# peacock3.net
KiCad netlist of a schematic drawn in EAGLE
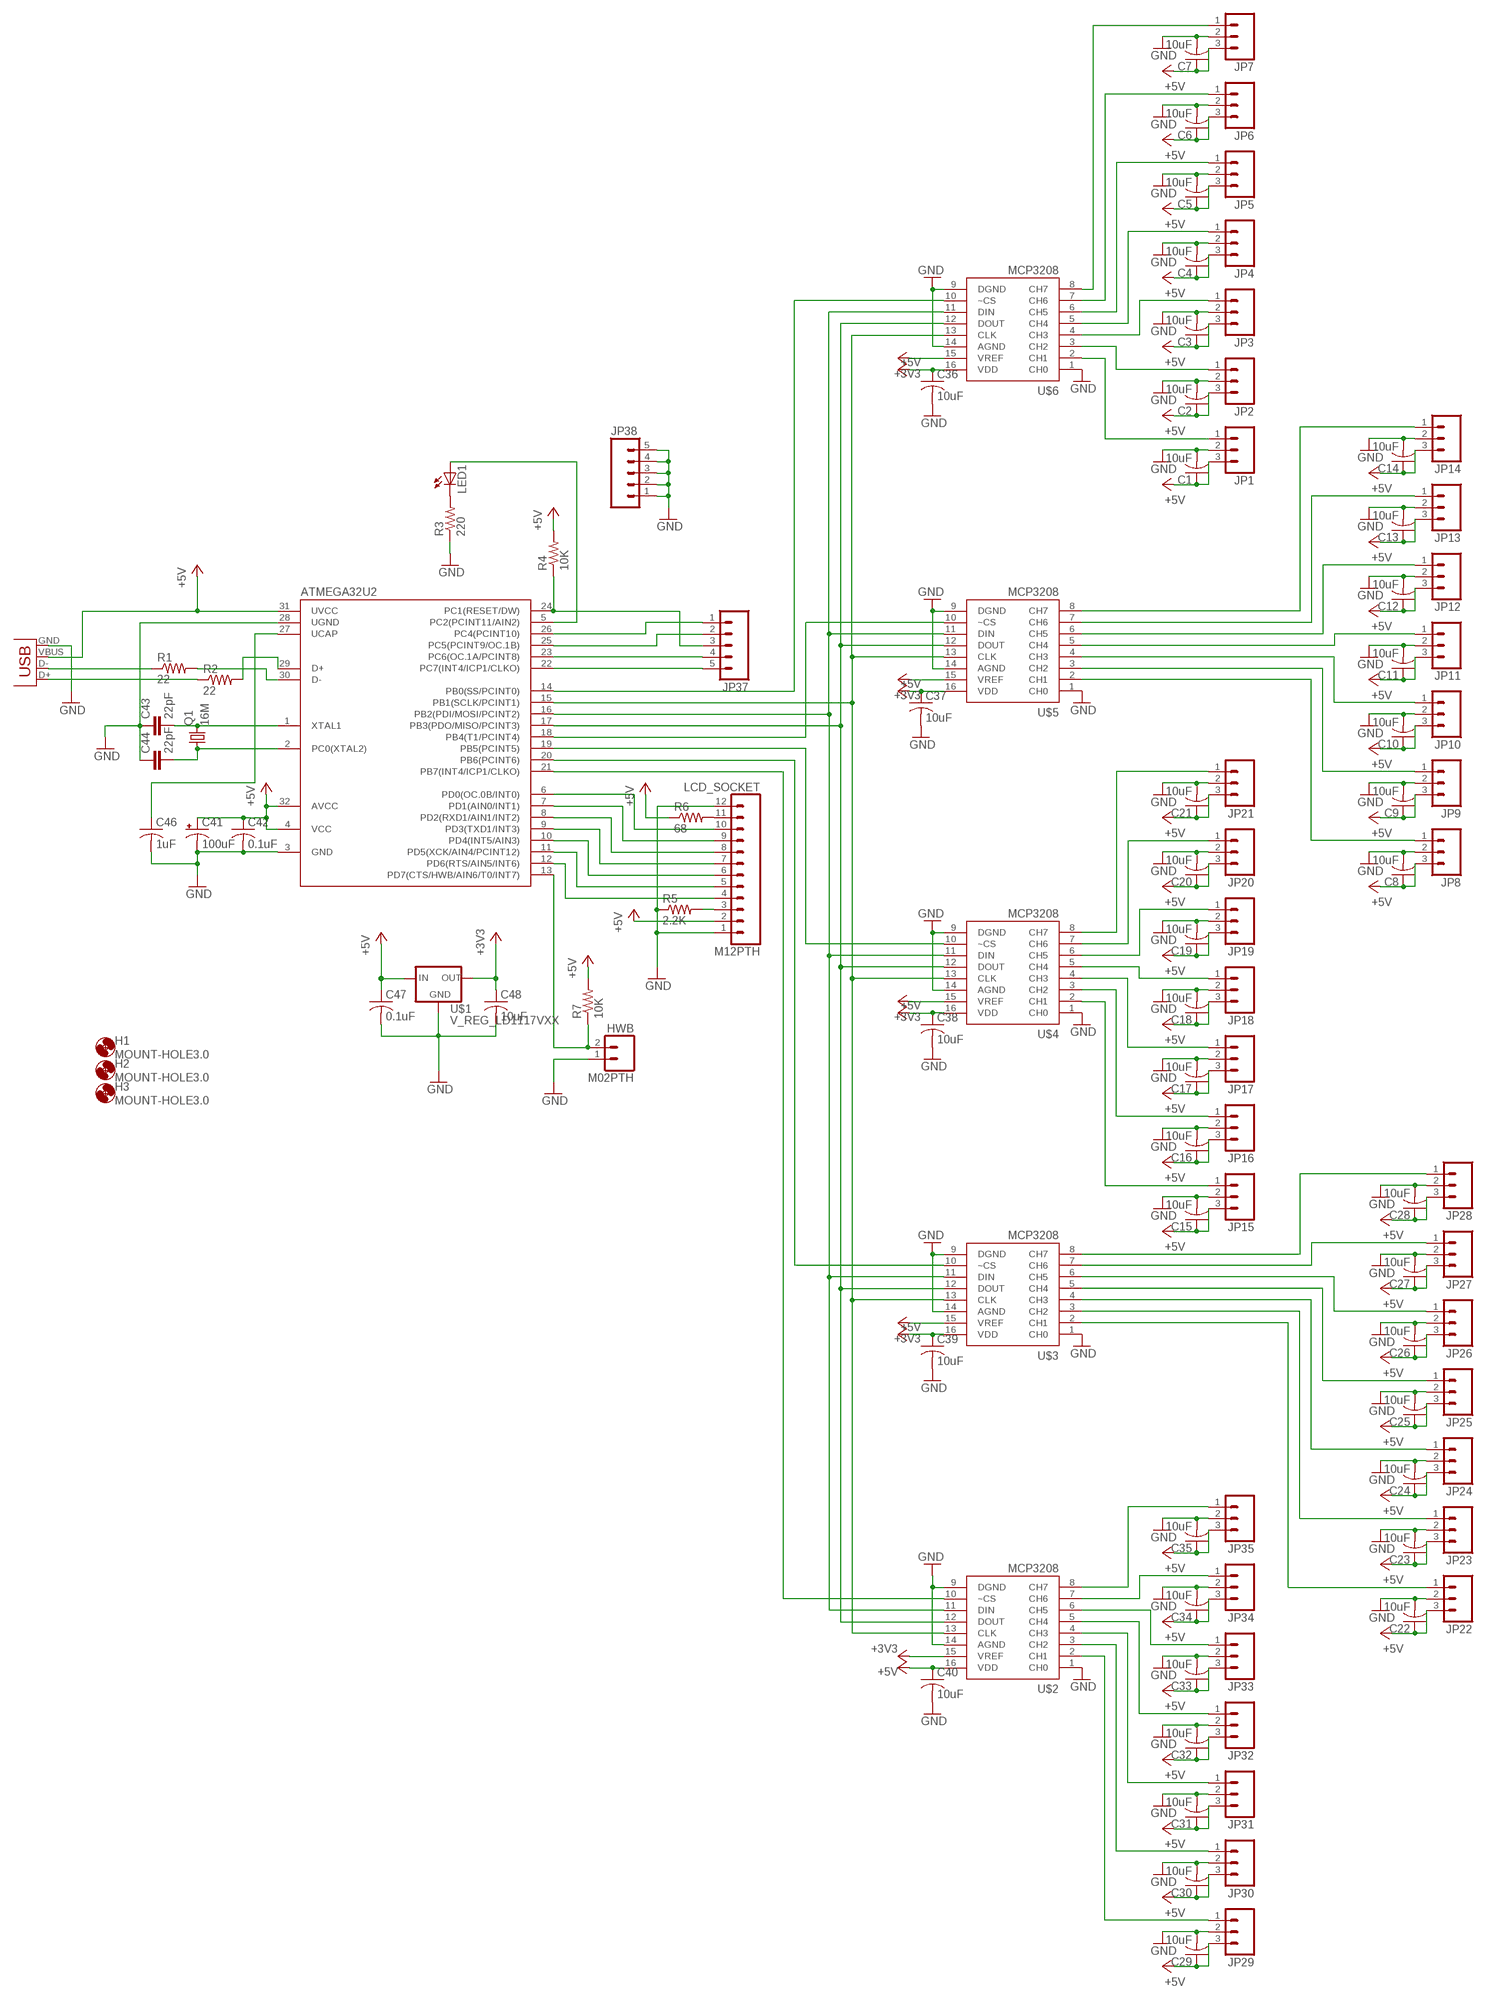
[diagram p0: schematic, sheet 1]

(export (version "E")
  (design (tool "Eeschema 10.0.6"))
  (components
    (comp (ref "ATMEGA32U2")
      (value "ATMEGA32U2")
      (footprint "eagle-import:TQFP32-08")
      (libsource (lib "eagle-import") (part "ATMEGA32U2"))
    )
    (comp (ref "C1")
      (value "10uF")
      (footprint "eagle-import:C1210")
      (libsource (lib "eagle-import") (part "C-USC1210"))
    )
    (comp (ref "C2")
      (value "10uF")
      (footprint "eagle-import:C1210")
      (libsource (lib "eagle-import") (part "C-USC1210"))
    )
    (comp (ref "C3")
      (value "10uF")
      (footprint "eagle-import:C1210")
      (libsource (lib "eagle-import") (part "C-USC1210"))
    )
    (comp (ref "C4")
      (value "10uF")
      (footprint "eagle-import:C1210")
      (libsource (lib "eagle-import") (part "C-USC1210"))
    )
    (comp (ref "C5")
      (value "10uF")
      (footprint "eagle-import:C1210")
      (libsource (lib "eagle-import") (part "C-USC1210"))
    )
    (comp (ref "C6")
      (value "10uF")
      (footprint "eagle-import:C1210")
      (libsource (lib "eagle-import") (part "C-USC1210"))
    )
    (comp (ref "C7")
      (value "10uF")
      (footprint "eagle-import:C1210")
      (libsource (lib "eagle-import") (part "C-USC1210"))
    )
    (comp (ref "C8")
      (value "10uF")
      (footprint "eagle-import:C1210")
      (libsource (lib "eagle-import") (part "C-USC1210"))
    )
    (comp (ref "C9")
      (value "10uF")
      (footprint "eagle-import:C1210")
      (libsource (lib "eagle-import") (part "C-USC1210"))
    )
    (comp (ref "C10")
      (value "10uF")
      (footprint "eagle-import:C1210")
      (libsource (lib "eagle-import") (part "C-USC1210"))
    )
    (comp (ref "C11")
      (value "10uF")
      (footprint "eagle-import:C1210")
      (libsource (lib "eagle-import") (part "C-USC1210"))
    )
    (comp (ref "C12")
      (value "10uF")
      (footprint "eagle-import:C1210")
      (libsource (lib "eagle-import") (part "C-USC1210"))
    )
    (comp (ref "C13")
      (value "10uF")
      (footprint "eagle-import:C1210")
      (libsource (lib "eagle-import") (part "C-USC1210"))
    )
    (comp (ref "C14")
      (value "10uF")
      (footprint "eagle-import:C1210")
      (libsource (lib "eagle-import") (part "C-USC1210"))
    )
    (comp (ref "C15")
      (value "10uF")
      (footprint "eagle-import:C1210")
      (libsource (lib "eagle-import") (part "C-USC1210"))
    )
    (comp (ref "C16")
      (value "10uF")
      (footprint "eagle-import:C1210")
      (libsource (lib "eagle-import") (part "C-USC1210"))
    )
    (comp (ref "C17")
      (value "10uF")
      (footprint "eagle-import:C1210")
      (libsource (lib "eagle-import") (part "C-USC1210"))
    )
    (comp (ref "C18")
      (value "10uF")
      (footprint "eagle-import:C1210")
      (libsource (lib "eagle-import") (part "C-USC1210"))
    )
    (comp (ref "C19")
      (value "10uF")
      (footprint "eagle-import:C1210")
      (libsource (lib "eagle-import") (part "C-USC1210"))
    )
    (comp (ref "C20")
      (value "10uF")
      (footprint "eagle-import:C1210")
      (libsource (lib "eagle-import") (part "C-USC1210"))
    )
    (comp (ref "C21")
      (value "10uF")
      (footprint "eagle-import:C1210")
      (libsource (lib "eagle-import") (part "C-USC1210"))
    )
    (comp (ref "C22")
      (value "10uF")
      (footprint "eagle-import:C1210")
      (libsource (lib "eagle-import") (part "C-USC1210"))
    )
    (comp (ref "C23")
      (value "10uF")
      (footprint "eagle-import:C1210")
      (libsource (lib "eagle-import") (part "C-USC1210"))
    )
    (comp (ref "C24")
      (value "10uF")
      (footprint "eagle-import:C1210")
      (libsource (lib "eagle-import") (part "C-USC1210"))
    )
    (comp (ref "C25")
      (value "10uF")
      (footprint "eagle-import:C1210")
      (libsource (lib "eagle-import") (part "C-USC1210"))
    )
    (comp (ref "C26")
      (value "10uF")
      (footprint "eagle-import:C1210")
      (libsource (lib "eagle-import") (part "C-USC1210"))
    )
    (comp (ref "C27")
      (value "10uF")
      (footprint "eagle-import:C1210")
      (libsource (lib "eagle-import") (part "C-USC1210"))
    )
    (comp (ref "C28")
      (value "10uF")
      (footprint "eagle-import:C1210")
      (libsource (lib "eagle-import") (part "C-USC1210"))
    )
    (comp (ref "C29")
      (value "10uF")
      (footprint "eagle-import:C1210")
      (libsource (lib "eagle-import") (part "C-USC1210"))
    )
    (comp (ref "C30")
      (value "10uF")
      (footprint "eagle-import:C1210")
      (libsource (lib "eagle-import") (part "C-USC1210"))
    )
    (comp (ref "C31")
      (value "10uF")
      (footprint "eagle-import:C1210")
      (libsource (lib "eagle-import") (part "C-USC1210"))
    )
    (comp (ref "C32")
      (value "10uF")
      (footprint "eagle-import:C1210")
      (libsource (lib "eagle-import") (part "C-USC1210"))
    )
    (comp (ref "C33")
      (value "10uF")
      (footprint "eagle-import:C1210")
      (libsource (lib "eagle-import") (part "C-USC1210"))
    )
    (comp (ref "C34")
      (value "10uF")
      (footprint "eagle-import:C1210")
      (libsource (lib "eagle-import") (part "C-USC1210"))
    )
    (comp (ref "C35")
      (value "10uF")
      (footprint "eagle-import:C1210")
      (libsource (lib "eagle-import") (part "C-USC1210"))
    )
    (comp (ref "C36")
      (value "10uF")
      (footprint "eagle-import:C1210")
      (libsource (lib "eagle-import") (part "C-USC1210"))
    )
    (comp (ref "C37")
      (value "10uF")
      (footprint "eagle-import:C1210")
      (libsource (lib "eagle-import") (part "C-USC1210"))
    )
    (comp (ref "C38")
      (value "10uF")
      (footprint "eagle-import:C1210")
      (libsource (lib "eagle-import") (part "C-USC1210"))
    )
    (comp (ref "C39")
      (value "10uF")
      (footprint "eagle-import:C1210")
      (libsource (lib "eagle-import") (part "C-USC1210"))
    )
    (comp (ref "C40")
      (value "10uF")
      (footprint "eagle-import:C1210")
      (libsource (lib "eagle-import") (part "C-USC1210"))
    )
    (comp (ref "C41")
      (value "100uF")
      (footprint "eagle-import:E5-6")
      (libsource (lib "eagle-import") (part "CPOL-USE5-6"))
    )
    (comp (ref "C42")
      (value "0.1uF")
      (footprint "eagle-import:C1210")
      (libsource (lib "eagle-import") (part "C-USC1210"))
    )
    (comp (ref "C43")
      (value "22pF")
      (footprint "eagle-import:C050-024X044")
      (libsource (lib "eagle-import") (part "C-EU050-024X044"))
    )
    (comp (ref "C44")
      (value "22pF")
      (footprint "eagle-import:C050-024X044")
      (libsource (lib "eagle-import") (part "C-EU050-024X044"))
    )
    (comp (ref "C46")
      (value "1uF")
      (footprint "eagle-import:C1210")
      (libsource (lib "eagle-import") (part "C-USC1210"))
    )
    (comp (ref "C47")
      (value "0.1uF")
      (footprint "eagle-import:C1210")
      (libsource (lib "eagle-import") (part "C-USC1210"))
    )
    (comp (ref "C48")
      (value "10uF")
      (footprint "eagle-import:C1210")
      (libsource (lib "eagle-import") (part "C-USC1210"))
    )
    (comp (ref "H1")
      (value "MOUNT-HOLE3.0")
      (footprint "eagle-import:3,0")
      (libsource (lib "eagle-import") (part "MOUNT-HOLE3.0"))
    )
    (comp (ref "H2")
      (value "MOUNT-HOLE3.0")
      (footprint "eagle-import:3,0")
      (libsource (lib "eagle-import") (part "MOUNT-HOLE3.0"))
    )
    (comp (ref "H3")
      (value "MOUNT-HOLE3.0")
      (footprint "eagle-import:3,0")
      (libsource (lib "eagle-import") (part "MOUNT-HOLE3.0"))
    )
    (comp (ref "HWB")
      (value "M02PTH")
      (footprint "eagle-import:1X02")
      (libsource (lib "eagle-import") (part "M02PTH"))
    )
    (comp (ref "JP1")
      (value "M03PTH")
      (footprint "eagle-import:1X03")
      (libsource (lib "eagle-import") (part "M03PTH"))
    )
    (comp (ref "JP2")
      (value "M03PTH")
      (footprint "eagle-import:1X03")
      (libsource (lib "eagle-import") (part "M03PTH"))
    )
    (comp (ref "JP3")
      (value "M03PTH")
      (footprint "eagle-import:1X03")
      (libsource (lib "eagle-import") (part "M03PTH"))
    )
    (comp (ref "JP4")
      (value "M03PTH")
      (footprint "eagle-import:1X03")
      (libsource (lib "eagle-import") (part "M03PTH"))
    )
    (comp (ref "JP5")
      (value "M03PTH")
      (footprint "eagle-import:1X03")
      (libsource (lib "eagle-import") (part "M03PTH"))
    )
    (comp (ref "JP6")
      (value "M03PTH")
      (footprint "eagle-import:1X03")
      (libsource (lib "eagle-import") (part "M03PTH"))
    )
    (comp (ref "JP7")
      (value "M03PTH")
      (footprint "eagle-import:1X03")
      (libsource (lib "eagle-import") (part "M03PTH"))
    )
    (comp (ref "JP8")
      (value "M03PTH")
      (footprint "eagle-import:1X03")
      (libsource (lib "eagle-import") (part "M03PTH"))
    )
    (comp (ref "JP9")
      (value "M03PTH")
      (footprint "eagle-import:1X03")
      (libsource (lib "eagle-import") (part "M03PTH"))
    )
    (comp (ref "JP10")
      (value "M03PTH")
      (footprint "eagle-import:1X03")
      (libsource (lib "eagle-import") (part "M03PTH"))
    )
    (comp (ref "JP11")
      (value "M03PTH")
      (footprint "eagle-import:1X03")
      (libsource (lib "eagle-import") (part "M03PTH"))
    )
    (comp (ref "JP12")
      (value "M03PTH")
      (footprint "eagle-import:1X03")
      (libsource (lib "eagle-import") (part "M03PTH"))
    )
    (comp (ref "JP13")
      (value "M03PTH")
      (footprint "eagle-import:1X03")
      (libsource (lib "eagle-import") (part "M03PTH"))
    )
    (comp (ref "JP14")
      (value "M03PTH")
      (footprint "eagle-import:1X03")
      (libsource (lib "eagle-import") (part "M03PTH"))
    )
    (comp (ref "JP15")
      (value "M03PTH")
      (footprint "eagle-import:1X03")
      (libsource (lib "eagle-import") (part "M03PTH"))
    )
    (comp (ref "JP16")
      (value "M03PTH")
      (footprint "eagle-import:1X03")
      (libsource (lib "eagle-import") (part "M03PTH"))
    )
    (comp (ref "JP17")
      (value "M03PTH")
      (footprint "eagle-import:1X03")
      (libsource (lib "eagle-import") (part "M03PTH"))
    )
    (comp (ref "JP18")
      (value "M03PTH")
      (footprint "eagle-import:1X03")
      (libsource (lib "eagle-import") (part "M03PTH"))
    )
    (comp (ref "JP19")
      (value "M03PTH")
      (footprint "eagle-import:1X03")
      (libsource (lib "eagle-import") (part "M03PTH"))
    )
    (comp (ref "JP20")
      (value "M03PTH")
      (footprint "eagle-import:1X03")
      (libsource (lib "eagle-import") (part "M03PTH"))
    )
    (comp (ref "JP21")
      (value "M03PTH")
      (footprint "eagle-import:1X03")
      (libsource (lib "eagle-import") (part "M03PTH"))
    )
    (comp (ref "JP22")
      (value "M03PTH")
      (footprint "eagle-import:1X03")
      (libsource (lib "eagle-import") (part "M03PTH"))
    )
    (comp (ref "JP23")
      (value "M03PTH")
      (footprint "eagle-import:1X03")
      (libsource (lib "eagle-import") (part "M03PTH"))
    )
    (comp (ref "JP24")
      (value "M03PTH")
      (footprint "eagle-import:1X03")
      (libsource (lib "eagle-import") (part "M03PTH"))
    )
    (comp (ref "JP25")
      (value "M03PTH")
      (footprint "eagle-import:1X03")
      (libsource (lib "eagle-import") (part "M03PTH"))
    )
    (comp (ref "JP26")
      (value "M03PTH")
      (footprint "eagle-import:1X03")
      (libsource (lib "eagle-import") (part "M03PTH"))
    )
    (comp (ref "JP27")
      (value "M03PTH")
      (footprint "eagle-import:1X03")
      (libsource (lib "eagle-import") (part "M03PTH"))
    )
    (comp (ref "JP28")
      (value "M03PTH")
      (footprint "eagle-import:1X03")
      (libsource (lib "eagle-import") (part "M03PTH"))
    )
    (comp (ref "JP29")
      (value "M03PTH")
      (footprint "eagle-import:1X03")
      (libsource (lib "eagle-import") (part "M03PTH"))
    )
    (comp (ref "JP30")
      (value "M03PTH")
      (footprint "eagle-import:1X03")
      (libsource (lib "eagle-import") (part "M03PTH"))
    )
    (comp (ref "JP31")
      (value "M03PTH")
      (footprint "eagle-import:1X03")
      (libsource (lib "eagle-import") (part "M03PTH"))
    )
    (comp (ref "JP32")
      (value "M03PTH")
      (footprint "eagle-import:1X03")
      (libsource (lib "eagle-import") (part "M03PTH"))
    )
    (comp (ref "JP33")
      (value "M03PTH")
      (footprint "eagle-import:1X03")
      (libsource (lib "eagle-import") (part "M03PTH"))
    )
    (comp (ref "JP34")
      (value "M03PTH")
      (footprint "eagle-import:1X03")
      (libsource (lib "eagle-import") (part "M03PTH"))
    )
    (comp (ref "JP35")
      (value "M03PTH")
      (footprint "eagle-import:1X03")
      (libsource (lib "eagle-import") (part "M03PTH"))
    )
    (comp (ref "JP36")
      (value "USB-B")
      (footprint "eagle-import:USB-B-PTH")
      (libsource (lib "eagle-import") (part "USBPTH"))
    )
    (comp (ref "JP37")
      (value "M05PTH")
      (footprint "eagle-import:1X05")
      (libsource (lib "eagle-import") (part "M05PTH"))
    )
    (comp (ref "JP38")
      (value "M05PTH")
      (footprint "eagle-import:1X05")
      (libsource (lib "eagle-import") (part "M05PTH"))
    )
    (comp (ref "LCD_SOCKET")
      (value "M12PTH")
      (footprint "eagle-import:1X12")
      (libsource (lib "eagle-import") (part "M12PTH"))
    )
    (comp (ref "LED1")
      (value "LED5MM")
      (footprint "eagle-import:LED5MM")
      (libsource (lib "eagle-import") (part "LED5MM"))
    )
    (comp (ref "Q1")
      (value "16M")
      (footprint "eagle-import:HC18U-V")
      (libsource (lib "eagle-import") (part "CRYSTALHC18U-V"))
    )
    (comp (ref "R1")
      (value "22")
      (footprint "eagle-import:0204_7")
      (libsource (lib "eagle-import") (part "R-US_0204/7"))
    )
    (comp (ref "R2")
      (value "22")
      (footprint "eagle-import:0204_7")
      (libsource (lib "eagle-import") (part "R-US_0204/7"))
    )
    (comp (ref "R3")
      (value "220")
      (footprint "eagle-import:0204_7")
      (libsource (lib "eagle-import") (part "R-US_0204/7"))
    )
    (comp (ref "R4")
      (value "10K")
      (footprint "eagle-import:0204_7")
      (libsource (lib "eagle-import") (part "R-US_0204/7"))
    )
    (comp (ref "R5")
      (value "2.2K")
      (footprint "eagle-import:0204_7")
      (libsource (lib "eagle-import") (part "R-US_0204/7"))
    )
    (comp (ref "R6")
      (value "68")
      (footprint "eagle-import:0204_7")
      (libsource (lib "eagle-import") (part "R-US_0204/7"))
    )
    (comp (ref "R7")
      (value "10K")
      (footprint "eagle-import:0204_7")
      (libsource (lib "eagle-import") (part "R-US_0204/7"))
    )
    (comp (ref "U$1")
      (value "V_REG_LD1117VXX")
      (footprint "eagle-import:78XXL")
      (libsource (lib "eagle-import") (part "V_REG_LD1117VXX"))
    )
    (comp (ref "U$2")
      (value "MCP3208")
      (footprint "eagle-import:SO16")
      (libsource (lib "eagle-import") (part "MCP3208"))
    )
    (comp (ref "U$3")
      (value "MCP3208")
      (footprint "eagle-import:SO16")
      (libsource (lib "eagle-import") (part "MCP3208"))
    )
    (comp (ref "U$4")
      (value "MCP3208")
      (footprint "eagle-import:SO16")
      (libsource (lib "eagle-import") (part "MCP3208"))
    )
    (comp (ref "U$5")
      (value "MCP3208")
      (footprint "eagle-import:SO16")
      (libsource (lib "eagle-import") (part "MCP3208"))
    )
    (comp (ref "U$6")
      (value "MCP3208")
      (footprint "eagle-import:SO16")
      (libsource (lib "eagle-import") (part "MCP3208"))
    )
  )
  (nets
    (net (code "1") (name "+3V3") (class "Default")
      (node (ref "C48") (pin "1") (pinfunction "1_1") (pintype "passive"))
      (node (ref "U$1") (pin "GND") (pinfunction "OUT_GND") (pintype "power_in"))
      (node (ref "U$2") (pin "15") (pinfunction "VREF_15") (pintype "bidirectional"))
      (node (ref "U$3") (pin "15") (pinfunction "VREF_15") (pintype "bidirectional"))
      (node (ref "U$4") (pin "15") (pinfunction "VREF_15") (pintype "bidirectional"))
      (node (ref "U$5") (pin "15") (pinfunction "VREF_15") (pintype "bidirectional"))
      (node (ref "U$6") (pin "15") (pinfunction "VREF_15") (pintype "bidirectional"))
    )
    (net (code "2") (name "+5V") (class "Default")
      (node (ref "ATMEGA32U2") (pin "31") (pinfunction "UVCC_31") (pintype "passive"))
      (node (ref "ATMEGA32U2") (pin "32") (pinfunction "AVCC_32") (pintype "passive"))
      (node (ref "ATMEGA32U2") (pin "4") (pinfunction "VCC_4") (pintype "power_in"))
      (node (ref "C1") (pin "1") (pinfunction "1_1") (pintype "passive"))
      (node (ref "C10") (pin "1") (pinfunction "1_1") (pintype "passive"))
      (node (ref "C11") (pin "1") (pinfunction "1_1") (pintype "passive"))
      (node (ref "C12") (pin "1") (pinfunction "1_1") (pintype "passive"))
      (node (ref "C13") (pin "1") (pinfunction "1_1") (pintype "passive"))
      (node (ref "C14") (pin "1") (pinfunction "1_1") (pintype "passive"))
      (node (ref "C15") (pin "1") (pinfunction "1_1") (pintype "passive"))
      (node (ref "C16") (pin "1") (pinfunction "1_1") (pintype "passive"))
      (node (ref "C17") (pin "1") (pinfunction "1_1") (pintype "passive"))
      (node (ref "C18") (pin "1") (pinfunction "1_1") (pintype "passive"))
      (node (ref "C19") (pin "1") (pinfunction "1_1") (pintype "passive"))
      (node (ref "C2") (pin "1") (pinfunction "1_1") (pintype "passive"))
      (node (ref "C20") (pin "1") (pinfunction "1_1") (pintype "passive"))
      (node (ref "C21") (pin "1") (pinfunction "1_1") (pintype "passive"))
      (node (ref "C22") (pin "1") (pinfunction "1_1") (pintype "passive"))
      (node (ref "C23") (pin "1") (pinfunction "1_1") (pintype "passive"))
      (node (ref "C24") (pin "1") (pinfunction "1_1") (pintype "passive"))
      (node (ref "C25") (pin "1") (pinfunction "1_1") (pintype "passive"))
      (node (ref "C26") (pin "1") (pinfunction "1_1") (pintype "passive"))
      (node (ref "C27") (pin "1") (pinfunction "1_1") (pintype "passive"))
      (node (ref "C28") (pin "1") (pinfunction "1_1") (pintype "passive"))
      (node (ref "C29") (pin "1") (pinfunction "1_1") (pintype "passive"))
      (node (ref "C3") (pin "1") (pinfunction "1_1") (pintype "passive"))
      (node (ref "C30") (pin "1") (pinfunction "1_1") (pintype "passive"))
      (node (ref "C31") (pin "1") (pinfunction "1_1") (pintype "passive"))
      (node (ref "C32") (pin "1") (pinfunction "1_1") (pintype "passive"))
      (node (ref "C33") (pin "1") (pinfunction "1_1") (pintype "passive"))
      (node (ref "C34") (pin "1") (pinfunction "1_1") (pintype "passive"))
      (node (ref "C35") (pin "1") (pinfunction "1_1") (pintype "passive"))
      (node (ref "C36") (pin "1") (pinfunction "1_1") (pintype "passive"))
      (node (ref "C37") (pin "1") (pinfunction "1_1") (pintype "passive"))
      (node (ref "C38") (pin "1") (pinfunction "1_1") (pintype "passive"))
      (node (ref "C39") (pin "1") (pinfunction "1_1") (pintype "passive"))
      (node (ref "C4") (pin "1") (pinfunction "1_1") (pintype "passive"))
      (node (ref "C40") (pin "1") (pinfunction "1_1") (pintype "passive"))
      (node (ref "C41") (pin "+") (pinfunction "+_+") (pintype "passive"))
      (node (ref "C42") (pin "1") (pinfunction "1_1") (pintype "passive"))
      (node (ref "C47") (pin "1") (pinfunction "1_1") (pintype "passive"))
      (node (ref "C5") (pin "1") (pinfunction "1_1") (pintype "passive"))
      (node (ref "C6") (pin "1") (pinfunction "1_1") (pintype "passive"))
      (node (ref "C7") (pin "1") (pinfunction "1_1") (pintype "passive"))
      (node (ref "C8") (pin "1") (pinfunction "1_1") (pintype "passive"))
      (node (ref "C9") (pin "1") (pinfunction "1_1") (pintype "passive"))
      (node (ref "JP1") (pin "3") (pinfunction "3_3") (pintype "passive"))
      (node (ref "JP10") (pin "3") (pinfunction "3_3") (pintype "passive"))
      (node (ref "JP11") (pin "3") (pinfunction "3_3") (pintype "passive"))
      (node (ref "JP12") (pin "3") (pinfunction "3_3") (pintype "passive"))
      (node (ref "JP13") (pin "3") (pinfunction "3_3") (pintype "passive"))
      (node (ref "JP14") (pin "3") (pinfunction "3_3") (pintype "passive"))
      (node (ref "JP15") (pin "3") (pinfunction "3_3") (pintype "passive"))
      (node (ref "JP16") (pin "3") (pinfunction "3_3") (pintype "passive"))
      (node (ref "JP17") (pin "3") (pinfunction "3_3") (pintype "passive"))
      (node (ref "JP18") (pin "3") (pinfunction "3_3") (pintype "passive"))
      (node (ref "JP19") (pin "3") (pinfunction "3_3") (pintype "passive"))
      (node (ref "JP2") (pin "3") (pinfunction "3_3") (pintype "passive"))
      (node (ref "JP20") (pin "3") (pinfunction "3_3") (pintype "passive"))
      (node (ref "JP21") (pin "3") (pinfunction "3_3") (pintype "passive"))
      (node (ref "JP22") (pin "3") (pinfunction "3_3") (pintype "passive"))
      (node (ref "JP23") (pin "3") (pinfunction "3_3") (pintype "passive"))
      (node (ref "JP24") (pin "3") (pinfunction "3_3") (pintype "passive"))
      (node (ref "JP25") (pin "3") (pinfunction "3_3") (pintype "passive"))
      (node (ref "JP26") (pin "3") (pinfunction "3_3") (pintype "passive"))
      (node (ref "JP27") (pin "3") (pinfunction "3_3") (pintype "passive"))
      (node (ref "JP28") (pin "3") (pinfunction "3_3") (pintype "passive"))
      (node (ref "JP29") (pin "3") (pinfunction "3_3") (pintype "passive"))
      (node (ref "JP3") (pin "3") (pinfunction "3_3") (pintype "passive"))
      (node (ref "JP30") (pin "3") (pinfunction "3_3") (pintype "passive"))
      (node (ref "JP31") (pin "3") (pinfunction "3_3") (pintype "passive"))
      (node (ref "JP32") (pin "3") (pinfunction "3_3") (pintype "passive"))
      (node (ref "JP33") (pin "3") (pinfunction "3_3") (pintype "passive"))
      (node (ref "JP34") (pin "3") (pinfunction "3_3") (pintype "passive"))
      (node (ref "JP35") (pin "3") (pinfunction "3_3") (pintype "passive"))
      (node (ref "JP36") (pin "VBUS") (pinfunction "VBUS_VBUS") (pintype "bidirectional"))
      (node (ref "JP4") (pin "3") (pinfunction "3_3") (pintype "passive"))
      (node (ref "JP5") (pin "3") (pinfunction "3_3") (pintype "passive"))
      (node (ref "JP6") (pin "3") (pinfunction "3_3") (pintype "passive"))
      (node (ref "JP7") (pin "3") (pinfunction "3_3") (pintype "passive"))
      (node (ref "JP8") (pin "3") (pinfunction "3_3") (pintype "passive"))
      (node (ref "JP9") (pin "3") (pinfunction "3_3") (pintype "passive"))
      (node (ref "LCD_SOCKET") (pin "2") (pinfunction "2_2") (pintype "passive"))
      (node (ref "R4") (pin "2") (pinfunction "2_2") (pintype "passive"))
      (node (ref "R6") (pin "1") (pinfunction "1_1") (pintype "passive"))
      (node (ref "R7") (pin "2") (pinfunction "2_2") (pintype "passive"))
      (node (ref "U$1") (pin "OUT") (pinfunction "IN_OUT") (pintype "input"))
      (node (ref "U$2") (pin "16") (pinfunction "VDD_16") (pintype "bidirectional"))
      (node (ref "U$3") (pin "16") (pinfunction "VDD_16") (pintype "bidirectional"))
      (node (ref "U$4") (pin "16") (pinfunction "VDD_16") (pintype "bidirectional"))
      (node (ref "U$5") (pin "16") (pinfunction "VDD_16") (pintype "bidirectional"))
      (node (ref "U$6") (pin "16") (pinfunction "VDD_16") (pintype "bidirectional"))
    )
    (net (code "3") (name "GND") (class "Default")
      (node (ref "ATMEGA32U2") (pin "28") (pinfunction "UGND_28") (pintype "passive"))
      (node (ref "ATMEGA32U2") (pin "3") (pinfunction "GND_3") (pintype "power_in"))
      (node (ref "C1") (pin "2") (pinfunction "2_2") (pintype "passive"))
      (node (ref "C10") (pin "2") (pinfunction "2_2") (pintype "passive"))
      (node (ref "C11") (pin "2") (pinfunction "2_2") (pintype "passive"))
      (node (ref "C12") (pin "2") (pinfunction "2_2") (pintype "passive"))
      (node (ref "C13") (pin "2") (pinfunction "2_2") (pintype "passive"))
      (node (ref "C14") (pin "2") (pinfunction "2_2") (pintype "passive"))
      (node (ref "C15") (pin "2") (pinfunction "2_2") (pintype "passive"))
      (node (ref "C16") (pin "2") (pinfunction "2_2") (pintype "passive"))
      (node (ref "C17") (pin "2") (pinfunction "2_2") (pintype "passive"))
      (node (ref "C18") (pin "2") (pinfunction "2_2") (pintype "passive"))
      (node (ref "C19") (pin "2") (pinfunction "2_2") (pintype "passive"))
      (node (ref "C2") (pin "2") (pinfunction "2_2") (pintype "passive"))
      (node (ref "C20") (pin "2") (pinfunction "2_2") (pintype "passive"))
      (node (ref "C21") (pin "2") (pinfunction "2_2") (pintype "passive"))
      (node (ref "C22") (pin "2") (pinfunction "2_2") (pintype "passive"))
      (node (ref "C23") (pin "2") (pinfunction "2_2") (pintype "passive"))
      (node (ref "C24") (pin "2") (pinfunction "2_2") (pintype "passive"))
      (node (ref "C25") (pin "2") (pinfunction "2_2") (pintype "passive"))
      (node (ref "C26") (pin "2") (pinfunction "2_2") (pintype "passive"))
      (node (ref "C27") (pin "2") (pinfunction "2_2") (pintype "passive"))
      (node (ref "C28") (pin "2") (pinfunction "2_2") (pintype "passive"))
      (node (ref "C29") (pin "2") (pinfunction "2_2") (pintype "passive"))
      (node (ref "C3") (pin "2") (pinfunction "2_2") (pintype "passive"))
      (node (ref "C30") (pin "2") (pinfunction "2_2") (pintype "passive"))
      (node (ref "C31") (pin "2") (pinfunction "2_2") (pintype "passive"))
      (node (ref "C32") (pin "2") (pinfunction "2_2") (pintype "passive"))
      (node (ref "C33") (pin "2") (pinfunction "2_2") (pintype "passive"))
      (node (ref "C34") (pin "2") (pinfunction "2_2") (pintype "passive"))
      (node (ref "C35") (pin "2") (pinfunction "2_2") (pintype "passive"))
      (node (ref "C36") (pin "2") (pinfunction "2_2") (pintype "passive"))
      (node (ref "C37") (pin "2") (pinfunction "2_2") (pintype "passive"))
      (node (ref "C38") (pin "2") (pinfunction "2_2") (pintype "passive"))
      (node (ref "C39") (pin "2") (pinfunction "2_2") (pintype "passive"))
      (node (ref "C4") (pin "2") (pinfunction "2_2") (pintype "passive"))
      (node (ref "C40") (pin "2") (pinfunction "2_2") (pintype "passive"))
      (node (ref "C41") (pin "-") (pinfunction "-_-") (pintype "passive"))
      (node (ref "C42") (pin "2") (pinfunction "2_2") (pintype "passive"))
      (node (ref "C43") (pin "1") (pinfunction "1_1") (pintype "passive"))
      (node (ref "C44") (pin "1") (pinfunction "1_1") (pintype "passive"))
      (node (ref "C46") (pin "2") (pinfunction "2_2") (pintype "passive"))
      (node (ref "C47") (pin "2") (pinfunction "2_2") (pintype "passive"))
      (node (ref "C48") (pin "2") (pinfunction "2_2") (pintype "passive"))
      (node (ref "C5") (pin "2") (pinfunction "2_2") (pintype "passive"))
      (node (ref "C6") (pin "2") (pinfunction "2_2") (pintype "passive"))
      (node (ref "C7") (pin "2") (pinfunction "2_2") (pintype "passive"))
      (node (ref "C8") (pin "2") (pinfunction "2_2") (pintype "passive"))
      (node (ref "C9") (pin "2") (pinfunction "2_2") (pintype "passive"))
      (node (ref "HWB") (pin "1") (pinfunction "1_1") (pintype "passive"))
      (node (ref "JP1") (pin "2") (pinfunction "2_2") (pintype "passive"))
      (node (ref "JP10") (pin "2") (pinfunction "2_2") (pintype "passive"))
      (node (ref "JP11") (pin "2") (pinfunction "2_2") (pintype "passive"))
      (node (ref "JP12") (pin "2") (pinfunction "2_2") (pintype "passive"))
      (node (ref "JP13") (pin "2") (pinfunction "2_2") (pintype "passive"))
      (node (ref "JP14") (pin "2") (pinfunction "2_2") (pintype "passive"))
      (node (ref "JP15") (pin "2") (pinfunction "2_2") (pintype "passive"))
      (node (ref "JP16") (pin "2") (pinfunction "2_2") (pintype "passive"))
      (node (ref "JP17") (pin "2") (pinfunction "2_2") (pintype "passive"))
      (node (ref "JP18") (pin "2") (pinfunction "2_2") (pintype "passive"))
      (node (ref "JP19") (pin "2") (pinfunction "2_2") (pintype "passive"))
      (node (ref "JP2") (pin "2") (pinfunction "2_2") (pintype "passive"))
      (node (ref "JP20") (pin "2") (pinfunction "2_2") (pintype "passive"))
      (node (ref "JP21") (pin "2") (pinfunction "2_2") (pintype "passive"))
      (node (ref "JP22") (pin "2") (pinfunction "2_2") (pintype "passive"))
      (node (ref "JP23") (pin "2") (pinfunction "2_2") (pintype "passive"))
      (node (ref "JP24") (pin "2") (pinfunction "2_2") (pintype "passive"))
      (node (ref "JP25") (pin "2") (pinfunction "2_2") (pintype "passive"))
      (node (ref "JP26") (pin "2") (pinfunction "2_2") (pintype "passive"))
      (node (ref "JP27") (pin "2") (pinfunction "2_2") (pintype "passive"))
      (node (ref "JP28") (pin "2") (pinfunction "2_2") (pintype "passive"))
      (node (ref "JP29") (pin "2") (pinfunction "2_2") (pintype "passive"))
      (node (ref "JP3") (pin "2") (pinfunction "2_2") (pintype "passive"))
      (node (ref "JP30") (pin "2") (pinfunction "2_2") (pintype "passive"))
      (node (ref "JP31") (pin "2") (pinfunction "2_2") (pintype "passive"))
      (node (ref "JP32") (pin "2") (pinfunction "2_2") (pintype "passive"))
      (node (ref "JP33") (pin "2") (pinfunction "2_2") (pintype "passive"))
      (node (ref "JP34") (pin "2") (pinfunction "2_2") (pintype "passive"))
      (node (ref "JP35") (pin "2") (pinfunction "2_2") (pintype "passive"))
      (node (ref "JP36") (pin "GND") (pinfunction "GND_GND") (pintype "bidirectional"))
      (node (ref "JP38") (pin "1") (pinfunction "1_1") (pintype "passive"))
      (node (ref "JP38") (pin "2") (pinfunction "2_2") (pintype "passive"))
      (node (ref "JP38") (pin "3") (pinfunction "3_3") (pintype "passive"))
      (node (ref "JP38") (pin "4") (pinfunction "4_4") (pintype "passive"))
      (node (ref "JP38") (pin "5") (pinfunction "5_5") (pintype "passive"))
      (node (ref "JP4") (pin "2") (pinfunction "2_2") (pintype "passive"))
      (node (ref "JP5") (pin "2") (pinfunction "2_2") (pintype "passive"))
      (node (ref "JP6") (pin "2") (pinfunction "2_2") (pintype "passive"))
      (node (ref "JP7") (pin "2") (pinfunction "2_2") (pintype "passive"))
      (node (ref "JP8") (pin "2") (pinfunction "2_2") (pintype "passive"))
      (node (ref "JP9") (pin "2") (pinfunction "2_2") (pintype "passive"))
      (node (ref "LCD_SOCKET") (pin "1") (pinfunction "1_1") (pintype "passive"))
      (node (ref "LCD_SOCKET") (pin "12") (pinfunction "12_12") (pintype "passive"))
      (node (ref "R3") (pin "1") (pinfunction "1_1") (pintype "passive"))
      (node (ref "R5") (pin "1") (pinfunction "1_1") (pintype "passive"))
      (node (ref "U$1") (pin "IN") (pinfunction "GND_IN") (pintype "input"))
      (node (ref "U$2") (pin "1") (pinfunction "CH0_1") (pintype "bidirectional"))
      (node (ref "U$2") (pin "14") (pinfunction "AGND_14") (pintype "bidirectional"))
      (node (ref "U$2") (pin "9") (pinfunction "DGND_9") (pintype "bidirectional"))
      (node (ref "U$3") (pin "1") (pinfunction "CH0_1") (pintype "bidirectional"))
      (node (ref "U$3") (pin "14") (pinfunction "AGND_14") (pintype "bidirectional"))
      (node (ref "U$3") (pin "9") (pinfunction "DGND_9") (pintype "bidirectional"))
      (node (ref "U$4") (pin "1") (pinfunction "CH0_1") (pintype "bidirectional"))
      (node (ref "U$4") (pin "14") (pinfunction "AGND_14") (pintype "bidirectional"))
      (node (ref "U$4") (pin "9") (pinfunction "DGND_9") (pintype "bidirectional"))
      (node (ref "U$5") (pin "1") (pinfunction "CH0_1") (pintype "bidirectional"))
      (node (ref "U$5") (pin "14") (pinfunction "AGND_14") (pintype "bidirectional"))
      (node (ref "U$5") (pin "9") (pinfunction "DGND_9") (pintype "bidirectional"))
      (node (ref "U$6") (pin "1") (pinfunction "CH0_1") (pintype "bidirectional"))
      (node (ref "U$6") (pin "14") (pinfunction "AGND_14") (pintype "bidirectional"))
      (node (ref "U$6") (pin "9") (pinfunction "DGND_9") (pintype "bidirectional"))
    )
    (net (code "4") (name "Net-(ATMEGA32U2-D+)") (class "Default")
      (node (ref "ATMEGA32U2") (pin "29") (pinfunction "D+_29") (pintype "passive"))
      (node (ref "R2") (pin "2") (pinfunction "2_2") (pintype "passive"))
    )
    (net (code "5") (name "Net-(ATMEGA32U2-D-)") (class "Default")
      (node (ref "ATMEGA32U2") (pin "30") (pinfunction "D-_30") (pintype "passive"))
      (node (ref "R1") (pin "2") (pinfunction "2_2") (pintype "passive"))
    )
    (net (code "6") (name "Net-(ATMEGA32U2-PB0(SS{slash}PCINT0))") (class "Default")
      (node (ref "ATMEGA32U2") (pin "14") (pinfunction "PB0(SS/PCINT0)_14") (pintype "bidirectional"))
      (node (ref "U$6") (pin "10") (pinfunction "~{CS}_10") (pintype "bidirectional"))
    )
    (net (code "7") (name "Net-(ATMEGA32U2-PB1(SCLK{slash}PCINT1))") (class "Default")
      (node (ref "ATMEGA32U2") (pin "15") (pinfunction "PB1(SCLK/PCINT1)_15") (pintype "bidirectional"))
      (node (ref "U$2") (pin "13") (pinfunction "CLK_13") (pintype "bidirectional"))
      (node (ref "U$3") (pin "13") (pinfunction "CLK_13") (pintype "bidirectional"))
      (node (ref "U$4") (pin "13") (pinfunction "CLK_13") (pintype "bidirectional"))
      (node (ref "U$5") (pin "13") (pinfunction "CLK_13") (pintype "bidirectional"))
      (node (ref "U$6") (pin "13") (pinfunction "CLK_13") (pintype "bidirectional"))
    )
    (net (code "8") (name "Net-(ATMEGA32U2-PB2(PDI{slash}MOSI{slash}PCINT2))") (class "Default")
      (node (ref "ATMEGA32U2") (pin "16") (pinfunction "PB2(PDI/MOSI/PCINT2)_16") (pintype "bidirectional"))
      (node (ref "U$2") (pin "11") (pinfunction "DIN_11") (pintype "bidirectional"))
      (node (ref "U$3") (pin "11") (pinfunction "DIN_11") (pintype "bidirectional"))
      (node (ref "U$4") (pin "11") (pinfunction "DIN_11") (pintype "bidirectional"))
      (node (ref "U$5") (pin "11") (pinfunction "DIN_11") (pintype "bidirectional"))
      (node (ref "U$6") (pin "11") (pinfunction "DIN_11") (pintype "bidirectional"))
    )
    (net (code "9") (name "Net-(ATMEGA32U2-PB3(PDO{slash}MISO{slash}PCINT3))") (class "Default")
      (node (ref "ATMEGA32U2") (pin "17") (pinfunction "PB3(PDO/MISO/PCINT3)_17") (pintype "bidirectional"))
      (node (ref "U$2") (pin "12") (pinfunction "DOUT_12") (pintype "bidirectional"))
      (node (ref "U$3") (pin "12") (pinfunction "DOUT_12") (pintype "bidirectional"))
      (node (ref "U$4") (pin "12") (pinfunction "DOUT_12") (pintype "bidirectional"))
      (node (ref "U$5") (pin "12") (pinfunction "DOUT_12") (pintype "bidirectional"))
      (node (ref "U$6") (pin "12") (pinfunction "DOUT_12") (pintype "bidirectional"))
    )
    (net (code "10") (name "Net-(ATMEGA32U2-PB4(T1{slash}PCINT4))") (class "Default")
      (node (ref "ATMEGA32U2") (pin "18") (pinfunction "PB4(T1/PCINT4)_18") (pintype "bidirectional"))
      (node (ref "U$5") (pin "10") (pinfunction "~{CS}_10") (pintype "bidirectional"))
    )
    (net (code "11") (name "Net-(ATMEGA32U2-PB5(PCINT5))") (class "Default")
      (node (ref "ATMEGA32U2") (pin "19") (pinfunction "PB5(PCINT5)_19") (pintype "bidirectional"))
      (node (ref "U$4") (pin "10") (pinfunction "~{CS}_10") (pintype "bidirectional"))
    )
    (net (code "12") (name "Net-(ATMEGA32U2-PB6(PCINT6))") (class "Default")
      (node (ref "ATMEGA32U2") (pin "20") (pinfunction "PB6(PCINT6)_20") (pintype "bidirectional"))
      (node (ref "U$3") (pin "10") (pinfunction "~{CS}_10") (pintype "bidirectional"))
    )
    (net (code "13") (name "Net-(ATMEGA32U2-PB7(INT4{slash}ICP1{slash}CLKO))") (class "Default")
      (node (ref "ATMEGA32U2") (pin "21") (pinfunction "PB7(INT4/ICP1/CLKO)_21") (pintype "bidirectional"))
      (node (ref "U$2") (pin "10") (pinfunction "~{CS}_10") (pintype "bidirectional"))
    )
    (net (code "14") (name "Net-(ATMEGA32U2-PC0(XTAL2))") (class "Default")
      (node (ref "ATMEGA32U2") (pin "2") (pinfunction "PC0(XTAL2)_2") (pintype "bidirectional"))
      (node (ref "C44") (pin "2") (pinfunction "2_2") (pintype "passive"))
      (node (ref "Q1") (pin "1") (pinfunction "1_1") (pintype "passive"))
    )
    (net (code "15") (name "Net-(ATMEGA32U2-PC1(RESET{slash}DW))") (class "Default")
      (node (ref "ATMEGA32U2") (pin "24") (pinfunction "PC1(RESET/DW)_24") (pintype "bidirectional"))
      (node (ref "JP37") (pin "3") (pinfunction "3_3") (pintype "passive"))
      (node (ref "R4") (pin "1") (pinfunction "1_1") (pintype "passive"))
    )
    (net (code "16") (name "Net-(ATMEGA32U2-PC2(PCINT11{slash}AIN2))") (class "Default")
      (node (ref "ATMEGA32U2") (pin "5") (pinfunction "PC2(PCINT11/AIN2)_5") (pintype "bidirectional"))
      (node (ref "LED1") (pin "A") (pinfunction "A_A") (pintype "passive"))
    )
    (net (code "17") (name "Net-(ATMEGA32U2-PC4(PCINT10))") (class "Default")
      (node (ref "ATMEGA32U2") (pin "26") (pinfunction "PC4(PCINT10)_26") (pintype "bidirectional"))
      (node (ref "JP37") (pin "1") (pinfunction "1_1") (pintype "passive"))
    )
    (net (code "18") (name "Net-(ATMEGA32U2-PC5(PCINT9{slash}OC.1B))") (class "Default")
      (node (ref "ATMEGA32U2") (pin "25") (pinfunction "PC5(PCINT9/OC.1B)_25") (pintype "bidirectional"))
      (node (ref "JP37") (pin "2") (pinfunction "2_2") (pintype "passive"))
    )
    (net (code "19") (name "Net-(ATMEGA32U2-PC6(OC.1A{slash}PCINT8))") (class "Default")
      (node (ref "ATMEGA32U2") (pin "23") (pinfunction "PC6(OC.1A/PCINT8)_23") (pintype "bidirectional"))
      (node (ref "JP37") (pin "4") (pinfunction "4_4") (pintype "passive"))
    )
    (net (code "20") (name "Net-(ATMEGA32U2-PC7(INT4{slash}ICP1{slash}CLKO))") (class "Default")
      (node (ref "ATMEGA32U2") (pin "22") (pinfunction "PC7(INT4/ICP1/CLKO)_22") (pintype "bidirectional"))
      (node (ref "JP37") (pin "5") (pinfunction "5_5") (pintype "passive"))
    )
    (net (code "21") (name "Net-(ATMEGA32U2-PD0(OC.0B{slash}INT0))") (class "Default")
      (node (ref "ATMEGA32U2") (pin "6") (pinfunction "PD0(OC.0B/INT0)_6") (pintype "bidirectional"))
      (node (ref "LCD_SOCKET") (pin "10") (pinfunction "10_10") (pintype "passive"))
    )
    (net (code "22") (name "Net-(ATMEGA32U2-PD1(AIN0{slash}INT1))") (class "Default")
      (node (ref "ATMEGA32U2") (pin "7") (pinfunction "PD1(AIN0/INT1)_7") (pintype "bidirectional"))
      (node (ref "LCD_SOCKET") (pin "9") (pinfunction "9_9") (pintype "passive"))
    )
    (net (code "23") (name "Net-(ATMEGA32U2-PD2(RXD1{slash}AIN1{slash}INT2))") (class "Default")
      (node (ref "ATMEGA32U2") (pin "8") (pinfunction "PD2(RXD1/AIN1/INT2)_8") (pintype "bidirectional"))
      (node (ref "LCD_SOCKET") (pin "8") (pinfunction "8_8") (pintype "passive"))
    )
    (net (code "24") (name "Net-(ATMEGA32U2-PD3(TXD1{slash}INT3))") (class "Default")
      (node (ref "ATMEGA32U2") (pin "9") (pinfunction "PD3(TXD1/INT3)_9") (pintype "bidirectional"))
      (node (ref "LCD_SOCKET") (pin "7") (pinfunction "7_7") (pintype "passive"))
    )
    (net (code "25") (name "Net-(ATMEGA32U2-PD4(INT5{slash}AIN3))") (class "Default")
      (node (ref "ATMEGA32U2") (pin "10") (pinfunction "PD4(INT5/AIN3)_10") (pintype "bidirectional"))
      (node (ref "LCD_SOCKET") (pin "6") (pinfunction "6_6") (pintype "passive"))
    )
    (net (code "26") (name "Net-(ATMEGA32U2-PD5(XCK{slash}AIN4{slash}PCINT12))") (class "Default")
      (node (ref "ATMEGA32U2") (pin "11") (pinfunction "PD5(XCK/AIN4/PCINT12)_11") (pintype "bidirectional"))
      (node (ref "LCD_SOCKET") (pin "5") (pinfunction "5_5") (pintype "passive"))
    )
    (net (code "27") (name "Net-(ATMEGA32U2-PD6(RTS{slash}AIN5{slash}INT6))") (class "Default")
      (node (ref "ATMEGA32U2") (pin "12") (pinfunction "PD6(RTS/AIN5/INT6)_12") (pintype "bidirectional"))
      (node (ref "LCD_SOCKET") (pin "4") (pinfunction "4_4") (pintype "passive"))
    )
    (net (code "28") (name "Net-(ATMEGA32U2-PD7(CTS{slash}HWB{slash}AIN6{slash}T0{slash}INT7))") (class "Default")
      (node (ref "ATMEGA32U2") (pin "13") (pinfunction "PD7(CTS/HWB/AIN6/T0/INT7)_13") (pintype "bidirectional"))
      (node (ref "HWB") (pin "2") (pinfunction "2_2") (pintype "passive"))
      (node (ref "R7") (pin "1") (pinfunction "1_1") (pintype "passive"))
    )
    (net (code "29") (name "Net-(ATMEGA32U2-UCAP)") (class "Default")
      (node (ref "ATMEGA32U2") (pin "27") (pinfunction "UCAP_27") (pintype "passive"))
      (node (ref "C46") (pin "1") (pinfunction "1_1") (pintype "passive"))
    )
    (net (code "30") (name "Net-(ATMEGA32U2-XTAL1)") (class "Default")
      (node (ref "ATMEGA32U2") (pin "1") (pinfunction "XTAL1_1") (pintype "bidirectional"))
      (node (ref "C43") (pin "2") (pinfunction "2_2") (pintype "passive"))
      (node (ref "Q1") (pin "2") (pinfunction "2_2") (pintype "passive"))
    )
    (net (code "31") (name "Net-(JP36-PadD+)") (class "Default")
      (node (ref "JP36") (pin "D+") (pinfunction "D+_D+") (pintype "bidirectional"))
      (node (ref "R2") (pin "1") (pinfunction "1_1") (pintype "passive"))
    )
    (net (code "32") (name "Net-(JP36-PadD-)") (class "Default")
      (node (ref "JP36") (pin "D-") (pinfunction "D-_D-") (pintype "bidirectional"))
      (node (ref "R1") (pin "1") (pinfunction "1_1") (pintype "passive"))
    )
    (net (code "33") (name "Net-(LCD_SOCKET-Pad3)") (class "Default")
      (node (ref "LCD_SOCKET") (pin "3") (pinfunction "3_3") (pintype "passive"))
      (node (ref "R5") (pin "2") (pinfunction "2_2") (pintype "passive"))
    )
    (net (code "34") (name "Net-(LCD_SOCKET-Pad11)") (class "Default")
      (node (ref "LCD_SOCKET") (pin "11") (pinfunction "11_11") (pintype "passive"))
      (node (ref "R6") (pin "2") (pinfunction "2_2") (pintype "passive"))
    )
    (net (code "35") (name "Net-(LED1-C)") (class "Default")
      (node (ref "LED1") (pin "K") (pinfunction "C_K") (pintype "passive"))
      (node (ref "R3") (pin "2") (pinfunction "2_2") (pintype "passive"))
    )
    (net (code "36") (name "Net-(U$2-CH1)") (class "Default")
      (node (ref "JP29") (pin "1") (pinfunction "1_1") (pintype "passive"))
      (node (ref "U$2") (pin "2") (pinfunction "CH1_2") (pintype "bidirectional"))
    )
    (net (code "37") (name "Net-(U$2-CH2)") (class "Default")
      (node (ref "JP30") (pin "1") (pinfunction "1_1") (pintype "passive"))
      (node (ref "U$2") (pin "3") (pinfunction "CH2_3") (pintype "bidirectional"))
    )
    (net (code "38") (name "Net-(U$2-CH3)") (class "Default")
      (node (ref "JP31") (pin "1") (pinfunction "1_1") (pintype "passive"))
      (node (ref "U$2") (pin "4") (pinfunction "CH3_4") (pintype "bidirectional"))
    )
    (net (code "39") (name "Net-(U$2-CH4)") (class "Default")
      (node (ref "JP32") (pin "1") (pinfunction "1_1") (pintype "passive"))
      (node (ref "U$2") (pin "5") (pinfunction "CH4_5") (pintype "bidirectional"))
    )
    (net (code "40") (name "Net-(U$2-CH5)") (class "Default")
      (node (ref "JP33") (pin "1") (pinfunction "1_1") (pintype "passive"))
      (node (ref "U$2") (pin "6") (pinfunction "CH5_6") (pintype "bidirectional"))
    )
    (net (code "41") (name "Net-(U$2-CH6)") (class "Default")
      (node (ref "JP34") (pin "1") (pinfunction "1_1") (pintype "passive"))
      (node (ref "U$2") (pin "7") (pinfunction "CH6_7") (pintype "bidirectional"))
    )
    (net (code "42") (name "Net-(U$2-CH7)") (class "Default")
      (node (ref "JP35") (pin "1") (pinfunction "1_1") (pintype "passive"))
      (node (ref "U$2") (pin "8") (pinfunction "CH7_8") (pintype "bidirectional"))
    )
    (net (code "43") (name "Net-(U$3-CH1)") (class "Default")
      (node (ref "JP22") (pin "1") (pinfunction "1_1") (pintype "passive"))
      (node (ref "U$3") (pin "2") (pinfunction "CH1_2") (pintype "bidirectional"))
    )
    (net (code "44") (name "Net-(U$3-CH2)") (class "Default")
      (node (ref "JP23") (pin "1") (pinfunction "1_1") (pintype "passive"))
      (node (ref "U$3") (pin "3") (pinfunction "CH2_3") (pintype "bidirectional"))
    )
    (net (code "45") (name "Net-(U$3-CH3)") (class "Default")
      (node (ref "JP24") (pin "1") (pinfunction "1_1") (pintype "passive"))
      (node (ref "U$3") (pin "4") (pinfunction "CH3_4") (pintype "bidirectional"))
    )
    (net (code "46") (name "Net-(U$3-CH4)") (class "Default")
      (node (ref "JP25") (pin "1") (pinfunction "1_1") (pintype "passive"))
      (node (ref "U$3") (pin "5") (pinfunction "CH4_5") (pintype "bidirectional"))
    )
    (net (code "47") (name "Net-(U$3-CH5)") (class "Default")
      (node (ref "JP26") (pin "1") (pinfunction "1_1") (pintype "passive"))
      (node (ref "U$3") (pin "6") (pinfunction "CH5_6") (pintype "bidirectional"))
    )
    (net (code "48") (name "Net-(U$3-CH6)") (class "Default")
      (node (ref "JP27") (pin "1") (pinfunction "1_1") (pintype "passive"))
      (node (ref "U$3") (pin "7") (pinfunction "CH6_7") (pintype "bidirectional"))
    )
    (net (code "49") (name "Net-(U$3-CH7)") (class "Default")
      (node (ref "JP28") (pin "1") (pinfunction "1_1") (pintype "passive"))
      (node (ref "U$3") (pin "8") (pinfunction "CH7_8") (pintype "bidirectional"))
    )
    (net (code "50") (name "Net-(U$4-CH1)") (class "Default")
      (node (ref "JP15") (pin "1") (pinfunction "1_1") (pintype "passive"))
      (node (ref "U$4") (pin "2") (pinfunction "CH1_2") (pintype "bidirectional"))
    )
    (net (code "51") (name "Net-(U$4-CH2)") (class "Default")
      (node (ref "JP16") (pin "1") (pinfunction "1_1") (pintype "passive"))
      (node (ref "U$4") (pin "3") (pinfunction "CH2_3") (pintype "bidirectional"))
    )
    (net (code "52") (name "Net-(U$4-CH3)") (class "Default")
      (node (ref "JP17") (pin "1") (pinfunction "1_1") (pintype "passive"))
      (node (ref "U$4") (pin "4") (pinfunction "CH3_4") (pintype "bidirectional"))
    )
    (net (code "53") (name "Net-(U$4-CH4)") (class "Default")
      (node (ref "JP18") (pin "1") (pinfunction "1_1") (pintype "passive"))
      (node (ref "U$4") (pin "5") (pinfunction "CH4_5") (pintype "bidirectional"))
    )
    (net (code "54") (name "Net-(U$4-CH5)") (class "Default")
      (node (ref "JP19") (pin "1") (pinfunction "1_1") (pintype "passive"))
      (node (ref "U$4") (pin "6") (pinfunction "CH5_6") (pintype "bidirectional"))
    )
    (net (code "55") (name "Net-(U$4-CH6)") (class "Default")
      (node (ref "JP20") (pin "1") (pinfunction "1_1") (pintype "passive"))
      (node (ref "U$4") (pin "7") (pinfunction "CH6_7") (pintype "bidirectional"))
    )
    (net (code "56") (name "Net-(U$4-CH7)") (class "Default")
      (node (ref "JP21") (pin "1") (pinfunction "1_1") (pintype "passive"))
      (node (ref "U$4") (pin "8") (pinfunction "CH7_8") (pintype "bidirectional"))
    )
    (net (code "57") (name "Net-(U$5-CH1)") (class "Default")
      (node (ref "JP8") (pin "1") (pinfunction "1_1") (pintype "passive"))
      (node (ref "U$5") (pin "2") (pinfunction "CH1_2") (pintype "bidirectional"))
    )
    (net (code "58") (name "Net-(U$5-CH2)") (class "Default")
      (node (ref "JP9") (pin "1") (pinfunction "1_1") (pintype "passive"))
      (node (ref "U$5") (pin "3") (pinfunction "CH2_3") (pintype "bidirectional"))
    )
    (net (code "59") (name "Net-(U$5-CH3)") (class "Default")
      (node (ref "JP10") (pin "1") (pinfunction "1_1") (pintype "passive"))
      (node (ref "U$5") (pin "4") (pinfunction "CH3_4") (pintype "bidirectional"))
    )
    (net (code "60") (name "Net-(U$5-CH4)") (class "Default")
      (node (ref "JP11") (pin "1") (pinfunction "1_1") (pintype "passive"))
      (node (ref "U$5") (pin "5") (pinfunction "CH4_5") (pintype "bidirectional"))
    )
    (net (code "61") (name "Net-(U$5-CH5)") (class "Default")
      (node (ref "JP12") (pin "1") (pinfunction "1_1") (pintype "passive"))
      (node (ref "U$5") (pin "6") (pinfunction "CH5_6") (pintype "bidirectional"))
    )
    (net (code "62") (name "Net-(U$5-CH6)") (class "Default")
      (node (ref "JP13") (pin "1") (pinfunction "1_1") (pintype "passive"))
      (node (ref "U$5") (pin "7") (pinfunction "CH6_7") (pintype "bidirectional"))
    )
    (net (code "63") (name "Net-(U$5-CH7)") (class "Default")
      (node (ref "JP14") (pin "1") (pinfunction "1_1") (pintype "passive"))
      (node (ref "U$5") (pin "8") (pinfunction "CH7_8") (pintype "bidirectional"))
    )
    (net (code "64") (name "Net-(U$6-CH1)") (class "Default")
      (node (ref "JP1") (pin "1") (pinfunction "1_1") (pintype "passive"))
      (node (ref "U$6") (pin "2") (pinfunction "CH1_2") (pintype "bidirectional"))
    )
    (net (code "65") (name "Net-(U$6-CH2)") (class "Default")
      (node (ref "JP2") (pin "1") (pinfunction "1_1") (pintype "passive"))
      (node (ref "U$6") (pin "3") (pinfunction "CH2_3") (pintype "bidirectional"))
    )
    (net (code "66") (name "Net-(U$6-CH3)") (class "Default")
      (node (ref "JP3") (pin "1") (pinfunction "1_1") (pintype "passive"))
      (node (ref "U$6") (pin "4") (pinfunction "CH3_4") (pintype "bidirectional"))
    )
    (net (code "67") (name "Net-(U$6-CH4)") (class "Default")
      (node (ref "JP4") (pin "1") (pinfunction "1_1") (pintype "passive"))
      (node (ref "U$6") (pin "5") (pinfunction "CH4_5") (pintype "bidirectional"))
    )
    (net (code "68") (name "Net-(U$6-CH5)") (class "Default")
      (node (ref "JP5") (pin "1") (pinfunction "1_1") (pintype "passive"))
      (node (ref "U$6") (pin "6") (pinfunction "CH5_6") (pintype "bidirectional"))
    )
    (net (code "69") (name "Net-(U$6-CH6)") (class "Default")
      (node (ref "JP6") (pin "1") (pinfunction "1_1") (pintype "passive"))
      (node (ref "U$6") (pin "7") (pinfunction "CH6_7") (pintype "bidirectional"))
    )
    (net (code "70") (name "Net-(U$6-CH7)") (class "Default")
      (node (ref "JP7") (pin "1") (pinfunction "1_1") (pintype "passive"))
      (node (ref "U$6") (pin "8") (pinfunction "CH7_8") (pintype "bidirectional"))
    )
  )
)
